# linux-H-zero.net
KiCad netlist of a schematic drawn in Altium Designer
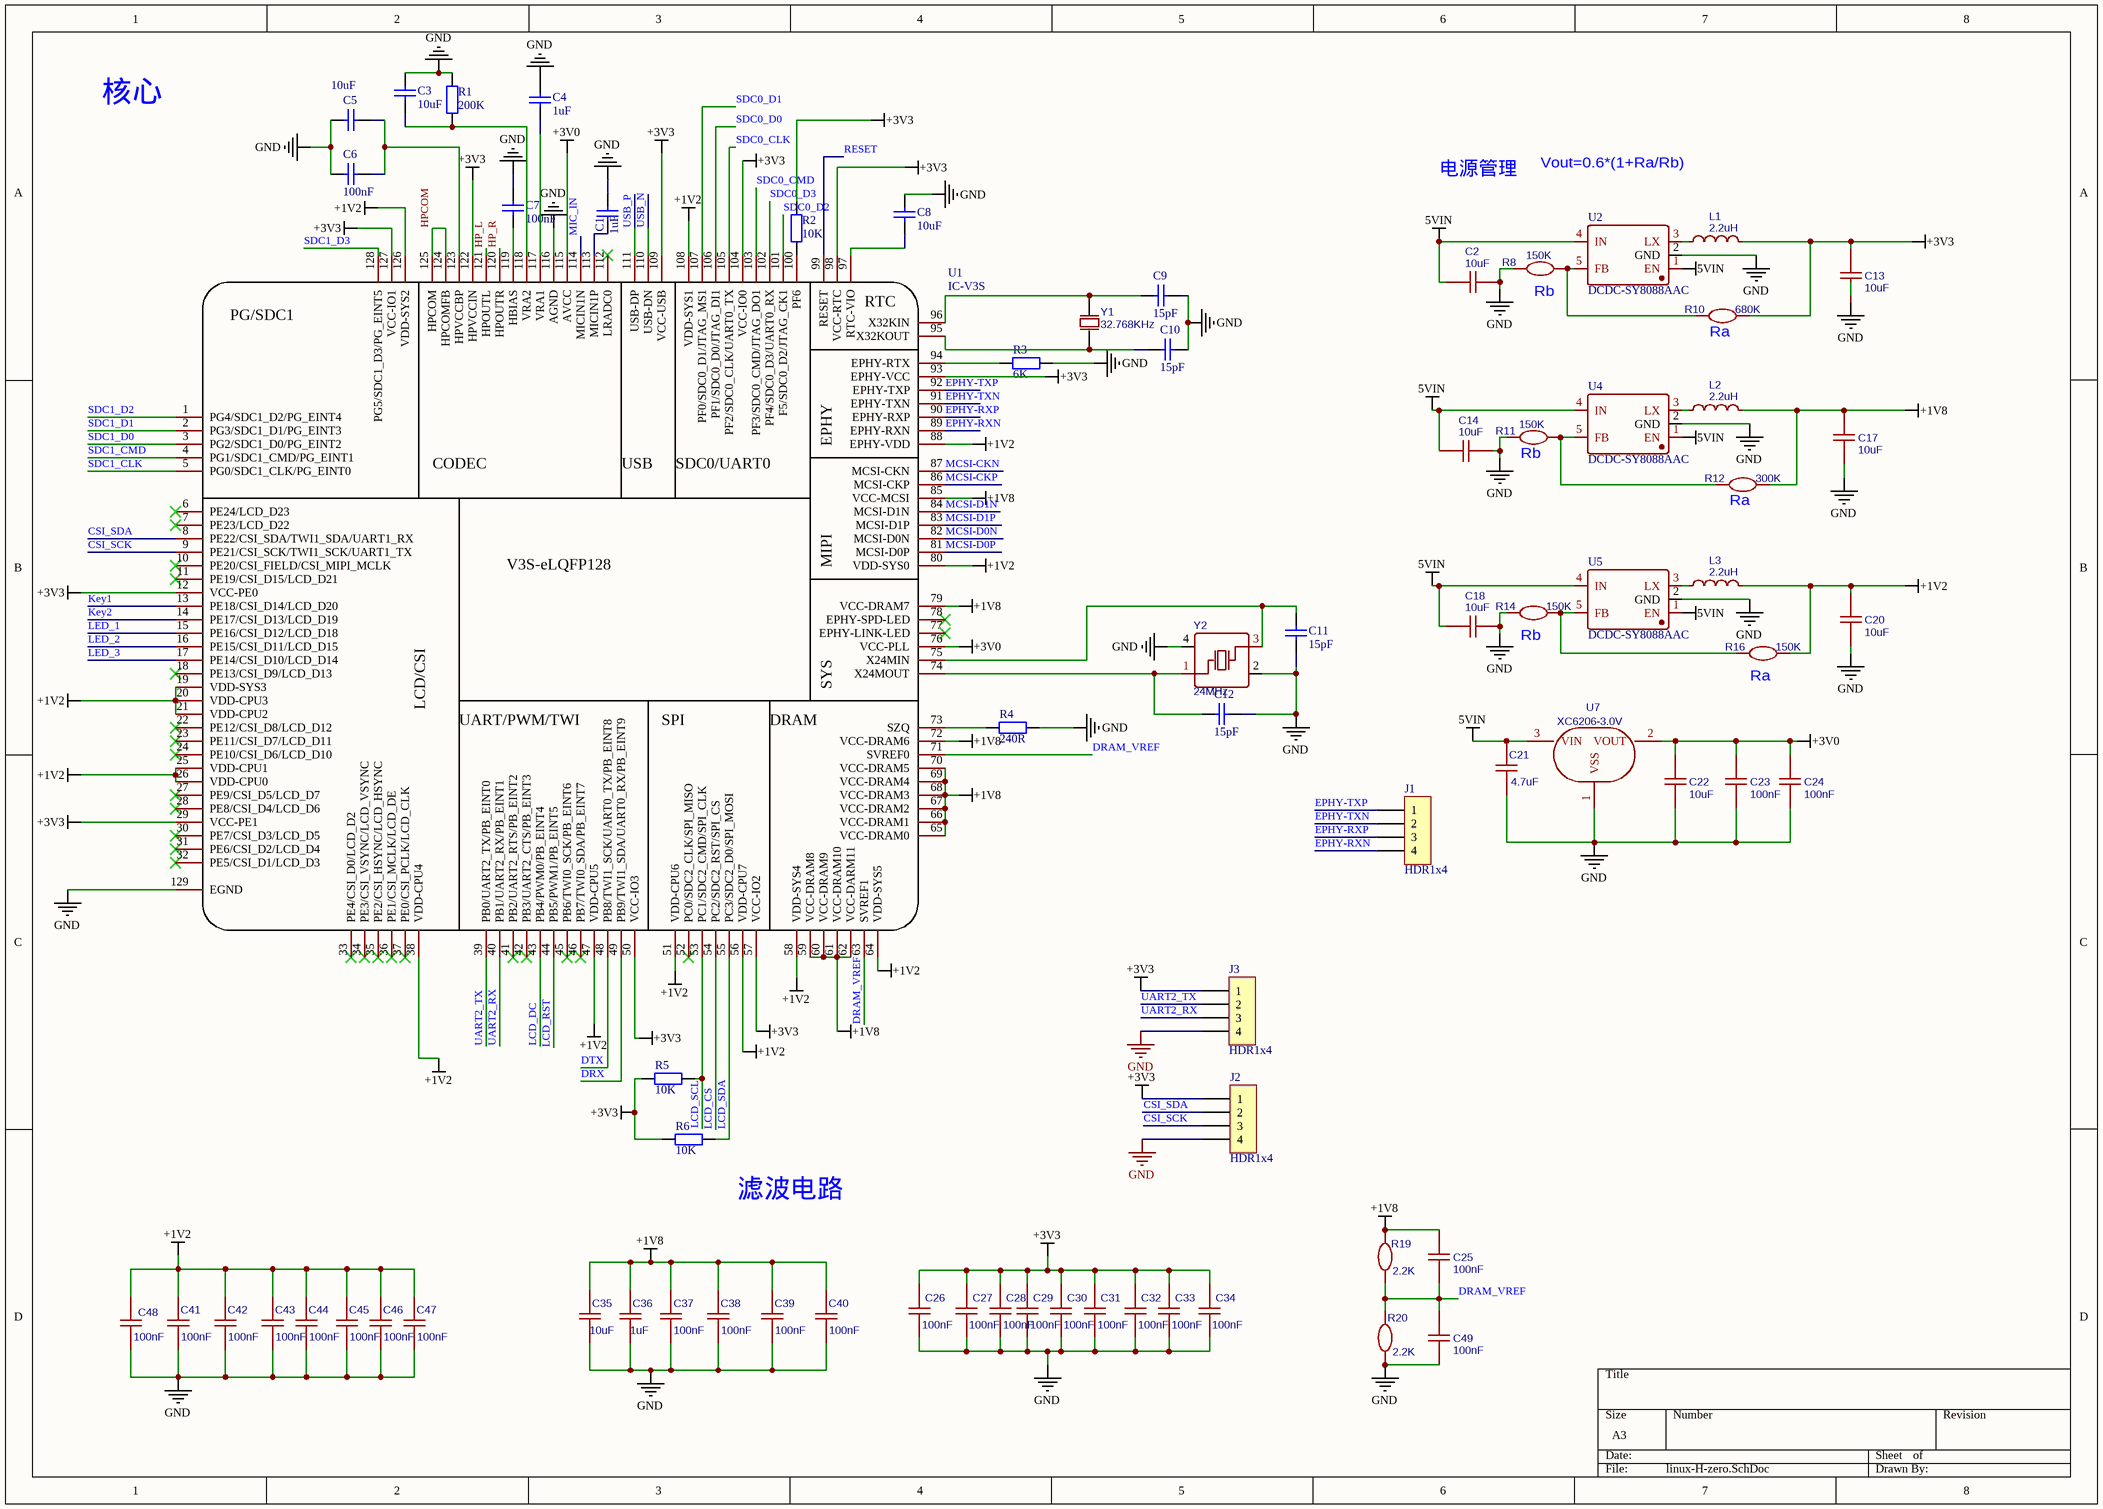
[diagram p0: linux-H-zero.SchDoc]

(export (version "E")
  (design (tool "Eeschema 10.0.6"))
  (components
    (comp (ref "C1") (value "1uF") (footprint "C0603-S") (libsource (lib "贴片") (part "C0603")))
    (comp (ref "C2")
      (value "10uF")
      (footprint "C0603-S")
      (fields
        (field (name "BOM_SUPPLIER PART") "C524952")
        (field (name "BOM_MANUFACTURER PART") "AMK107BJ106MA-T")
        (field (name "CONTRIBUTOR") "LCSC")
      )
      (libsource (lib "altium-import") (part "root_0_10uF_"))
    )
    (comp (ref "C3") (value "10uF") (footprint "C0603-S") (libsource (lib "贴片") (part "C0603")))
    (comp (ref "C4") (value "1uF") (footprint "C0603-S") (libsource (lib "贴片") (part "C0603")))
    (comp (ref "C5") (value "10uF") (footprint "C0603-S") (libsource (lib "贴片") (part "C0603")))
    (comp (ref "C6") (value "100nF") (footprint "C0603-S") (libsource (lib "贴片") (part "C0603")))
    (comp (ref "C7") (value "100nF") (footprint "C0603-S") (libsource (lib "贴片") (part "C0603")))
    (comp (ref "C8") (value "10uF") (footprint "C0603-S") (libsource (lib "贴片") (part "C0603")))
    (comp (ref "C9") (value "15pF") (footprint "C0603-S") (libsource (lib "贴片") (part "C0603")))
    (comp (ref "C10") (value "15pF") (footprint "C0603-S") (libsource (lib "贴片") (part "C0603")))
    (comp (ref "C11") (value "15pF") (footprint "C0603-S") (libsource (lib "贴片") (part "C0603")))
    (comp (ref "C12") (value "15pF") (footprint "C0603-S") (libsource (lib "贴片") (part "C0603")))
    (comp (ref "C13")
      (value "10uF")
      (footprint "C0603-S")
      (fields
        (field (name "BOM_SUPPLIER PART") "C524952")
        (field (name "BOM_MANUFACTURER PART") "AMK107BJ106MA-T")
        (field (name "CONTRIBUTOR") "LCSC")
      )
      (libsource (lib "altium-import") (part "root_1_10uF_"))
    )
    (comp (ref "C14")
      (value "10uF")
      (footprint "C0603-S")
      (fields
        (field (name "BOM_SUPPLIER PART") "C524952")
        (field (name "BOM_MANUFACTURER PART") "AMK107BJ106MA-T")
        (field (name "CONTRIBUTOR") "LCSC")
      )
      (libsource (lib "altium-import") (part "root_0_10uF_"))
    )
    (comp (ref "C17")
      (value "10uF")
      (footprint "C0603-S")
      (fields
        (field (name "BOM_SUPPLIER PART") "C524952")
        (field (name "BOM_MANUFACTURER PART") "AMK107BJ106MA-T")
        (field (name "CONTRIBUTOR") "LCSC")
      )
      (libsource (lib "altium-import") (part "root_1_10uF_"))
    )
    (comp (ref "C18")
      (value "10uF")
      (footprint "C0603-S")
      (fields
        (field (name "BOM_SUPPLIER PART") "C524952")
        (field (name "BOM_MANUFACTURER PART") "AMK107BJ106MA-T")
        (field (name "CONTRIBUTOR") "LCSC")
      )
      (libsource (lib "altium-import") (part "root_0_10uF_"))
    )
    (comp (ref "C20")
      (value "10uF")
      (footprint "C0603-S")
      (fields
        (field (name "BOM_SUPPLIER PART") "C524952")
        (field (name "BOM_MANUFACTURER PART") "AMK107BJ106MA-T")
        (field (name "CONTRIBUTOR") "LCSC")
      )
      (libsource (lib "altium-import") (part "root_1_10uF_"))
    )
    (comp (ref "C21")
      (value "4.7uF")
      (footprint "C0603-S")
      (fields
        (field (name "BOM_SUPPLIER PART") "C524952")
        (field (name "BOM_MANUFACTURER PART") "AMK107BJ106MA-T")
        (field (name "CONTRIBUTOR") "LCSC")
      )
      (libsource (lib "altium-import") (part "root_1_4.7uF_"))
    )
    (comp (ref "C22")
      (value "10uF")
      (footprint "C0603-S")
      (fields
        (field (name "BOM_SUPPLIER PART") "C524952")
        (field (name "BOM_MANUFACTURER PART") "AMK107BJ106MA-T")
        (field (name "CONTRIBUTOR") "LCSC")
      )
      (libsource (lib "altium-import") (part "root_1_10uF_"))
    )
    (comp (ref "C23")
      (value "100nF")
      (footprint "C0603-S")
      (fields
        (field (name "BOM_SUPPLIER PART") "C524952")
        (field (name "BOM_MANUFACTURER PART") "AMK107BJ106MA-T")
        (field (name "CONTRIBUTOR") "LCSC")
      )
      (libsource (lib "altium-import") (part "root_1_100nF_"))
    )
    (comp (ref "C24")
      (value "100nF")
      (footprint "C0603-S")
      (fields
        (field (name "BOM_SUPPLIER PART") "C524952")
        (field (name "BOM_MANUFACTURER PART") "AMK107BJ106MA-T")
        (field (name "CONTRIBUTOR") "LCSC")
      )
      (libsource (lib "altium-import") (part "root_1_100nF_"))
    )
    (comp (ref "C25")
      (value "100nF")
      (footprint "C0603-S")
      (fields
        (field (name "BOM_SUPPLIER PART") "C524952")
        (field (name "BOM_MANUFACTURER PART") "AMK107BJ106MA-T")
        (field (name "CONTRIBUTOR") "LCSC")
      )
      (libsource (lib "altium-import") (part "root_1_100nF_"))
    )
    (comp (ref "C26")
      (value "100nF")
      (footprint "C0603-S")
      (fields
        (field (name "BOM_SUPPLIER PART") "C524952")
        (field (name "BOM_MANUFACTURER PART") "AMK107BJ106MA-T")
        (field (name "CONTRIBUTOR") "LCSC")
      )
      (libsource (lib "altium-import") (part "root_3_100nF_"))
    )
    (comp (ref "C27")
      (value "100nF")
      (footprint "C0603-S")
      (fields
        (field (name "BOM_SUPPLIER PART") "C524952")
        (field (name "BOM_MANUFACTURER PART") "AMK107BJ106MA-T")
        (field (name "CONTRIBUTOR") "LCSC")
      )
      (libsource (lib "altium-import") (part "root_3_100nF_"))
    )
    (comp (ref "C28")
      (value "100nF")
      (footprint "C0603-S")
      (fields
        (field (name "BOM_SUPPLIER PART") "C524952")
        (field (name "BOM_MANUFACTURER PART") "AMK107BJ106MA-T")
        (field (name "CONTRIBUTOR") "LCSC")
      )
      (libsource (lib "altium-import") (part "root_3_100nF_"))
    )
    (comp (ref "C29")
      (value "100nF")
      (footprint "C0603-S")
      (fields
        (field (name "BOM_SUPPLIER PART") "C524952")
        (field (name "BOM_MANUFACTURER PART") "AMK107BJ106MA-T")
        (field (name "CONTRIBUTOR") "LCSC")
      )
      (libsource (lib "altium-import") (part "root_3_100nF_"))
    )
    (comp (ref "C30")
      (value "100nF")
      (footprint "C0603-S")
      (fields
        (field (name "BOM_SUPPLIER PART") "C524952")
        (field (name "BOM_MANUFACTURER PART") "AMK107BJ106MA-T")
        (field (name "CONTRIBUTOR") "LCSC")
      )
      (libsource (lib "altium-import") (part "root_3_100nF_"))
    )
    (comp (ref "C31")
      (value "100nF")
      (footprint "C0603-S")
      (fields
        (field (name "BOM_SUPPLIER PART") "C524952")
        (field (name "BOM_MANUFACTURER PART") "AMK107BJ106MA-T")
        (field (name "CONTRIBUTOR") "LCSC")
      )
      (libsource (lib "altium-import") (part "root_3_100nF_"))
    )
    (comp (ref "C32")
      (value "100nF")
      (footprint "C0603-S")
      (fields
        (field (name "BOM_SUPPLIER PART") "C524952")
        (field (name "BOM_MANUFACTURER PART") "AMK107BJ106MA-T")
        (field (name "CONTRIBUTOR") "LCSC")
      )
      (libsource (lib "altium-import") (part "root_3_100nF_"))
    )
    (comp (ref "C33")
      (value "100nF")
      (footprint "C0603-S")
      (fields
        (field (name "BOM_SUPPLIER PART") "C524952")
        (field (name "BOM_MANUFACTURER PART") "AMK107BJ106MA-T")
        (field (name "CONTRIBUTOR") "LCSC")
      )
      (libsource (lib "altium-import") (part "root_3_100nF_"))
    )
    (comp (ref "C34")
      (value "100nF")
      (footprint "C0603-S")
      (fields
        (field (name "BOM_SUPPLIER PART") "C524952")
        (field (name "BOM_MANUFACTURER PART") "AMK107BJ106MA-T")
        (field (name "CONTRIBUTOR") "LCSC")
      )
      (libsource (lib "altium-import") (part "root_3_100nF_"))
    )
    (comp (ref "C35")
      (value "10uF")
      (footprint "C0603-S")
      (fields
        (field (name "BOM_SUPPLIER PART") "C524952")
        (field (name "BOM_MANUFACTURER PART") "AMK107BJ106MA-T")
        (field (name "CONTRIBUTOR") "LCSC")
      )
      (libsource (lib "altium-import") (part "root_1_10uF_"))
    )
    (comp (ref "C36")
      (value "1uF")
      (footprint "C0603-S")
      (fields
        (field (name "BOM_SUPPLIER PART") "C524952")
        (field (name "BOM_MANUFACTURER PART") "AMK107BJ106MA-T")
        (field (name "CONTRIBUTOR") "LCSC")
      )
      (libsource (lib "altium-import") (part "root_1_1uF_"))
    )
    (comp (ref "C37")
      (value "100nF")
      (footprint "C0603-S")
      (fields
        (field (name "BOM_SUPPLIER PART") "C524952")
        (field (name "BOM_MANUFACTURER PART") "AMK107BJ106MA-T")
        (field (name "CONTRIBUTOR") "LCSC")
      )
      (libsource (lib "altium-import") (part "root_1_100nF_"))
    )
    (comp (ref "C38")
      (value "100nF")
      (footprint "C0603-S")
      (fields
        (field (name "BOM_SUPPLIER PART") "C524952")
        (field (name "BOM_MANUFACTURER PART") "AMK107BJ106MA-T")
        (field (name "CONTRIBUTOR") "LCSC")
      )
      (libsource (lib "altium-import") (part "root_1_100nF_"))
    )
    (comp (ref "C39")
      (value "100nF")
      (footprint "C0603-S")
      (fields
        (field (name "BOM_SUPPLIER PART") "C524952")
        (field (name "BOM_MANUFACTURER PART") "AMK107BJ106MA-T")
        (field (name "CONTRIBUTOR") "LCSC")
      )
      (libsource (lib "altium-import") (part "root_1_100nF_"))
    )
    (comp (ref "C40")
      (value "100nF")
      (footprint "C0603-S")
      (fields
        (field (name "BOM_SUPPLIER PART") "C524952")
        (field (name "BOM_MANUFACTURER PART") "AMK107BJ106MA-T")
        (field (name "CONTRIBUTOR") "LCSC")
      )
      (libsource (lib "altium-import") (part "root_1_100nF_"))
    )
    (comp (ref "C41")
      (value "100nF")
      (footprint "C0603-S")
      (fields
        (field (name "BOM_SUPPLIER PART") "C524952")
        (field (name "BOM_MANUFACTURER PART") "AMK107BJ106MA-T")
        (field (name "CONTRIBUTOR") "LCSC")
      )
      (libsource (lib "altium-import") (part "root_1_100nF_"))
    )
    (comp (ref "C42")
      (value "100nF")
      (footprint "C0603-S")
      (fields
        (field (name "BOM_SUPPLIER PART") "C524952")
        (field (name "BOM_MANUFACTURER PART") "AMK107BJ106MA-T")
        (field (name "CONTRIBUTOR") "LCSC")
      )
      (libsource (lib "altium-import") (part "root_1_100nF_"))
    )
    (comp (ref "C43")
      (value "100nF")
      (footprint "C0603-S")
      (fields
        (field (name "BOM_SUPPLIER PART") "C524952")
        (field (name "BOM_MANUFACTURER PART") "AMK107BJ106MA-T")
        (field (name "CONTRIBUTOR") "LCSC")
      )
      (libsource (lib "altium-import") (part "root_1_100nF_"))
    )
    (comp (ref "C44")
      (value "100nF")
      (footprint "C0603-S")
      (fields
        (field (name "BOM_SUPPLIER PART") "C524952")
        (field (name "BOM_MANUFACTURER PART") "AMK107BJ106MA-T")
        (field (name "CONTRIBUTOR") "LCSC")
      )
      (libsource (lib "altium-import") (part "root_1_100nF_"))
    )
    (comp (ref "C45")
      (value "100nF")
      (footprint "C0603-S")
      (fields
        (field (name "BOM_SUPPLIER PART") "C524952")
        (field (name "BOM_MANUFACTURER PART") "AMK107BJ106MA-T")
        (field (name "CONTRIBUTOR") "LCSC")
      )
      (libsource (lib "altium-import") (part "root_1_100nF_"))
    )
    (comp (ref "C46")
      (value "100nF")
      (footprint "C0603-S")
      (fields
        (field (name "BOM_SUPPLIER PART") "C524952")
        (field (name "BOM_MANUFACTURER PART") "AMK107BJ106MA-T")
        (field (name "CONTRIBUTOR") "LCSC")
      )
      (libsource (lib "altium-import") (part "root_1_100nF_"))
    )
    (comp (ref "C47")
      (value "100nF")
      (footprint "C0603-S")
      (fields
        (field (name "BOM_SUPPLIER PART") "C524952")
        (field (name "BOM_MANUFACTURER PART") "AMK107BJ106MA-T")
        (field (name "CONTRIBUTOR") "LCSC")
      )
      (libsource (lib "altium-import") (part "root_1_100nF_"))
    )
    (comp (ref "C48")
      (value "100nF")
      (footprint "C0603-S")
      (fields
        (field (name "BOM_SUPPLIER PART") "C524952")
        (field (name "BOM_MANUFACTURER PART") "AMK107BJ106MA-T")
        (field (name "CONTRIBUTOR") "LCSC")
      )
      (libsource (lib "altium-import") (part "root_1_100nF_"))
    )
    (comp (ref "C49")
      (value "100nF")
      (footprint "C0603-S")
      (fields
        (field (name "BOM_SUPPLIER PART") "C524952")
        (field (name "BOM_MANUFACTURER PART") "AMK107BJ106MA-T")
        (field (name "CONTRIBUTOR") "LCSC")
      )
      (libsource (lib "altium-import") (part "root_1_100nF_"))
    )
    (comp (ref "J1")
      (value "HDR1x4")
      (footprint "T-4PIN")
      (description "Connector")
      (libsource (lib "插件") (part "HDR1x4"))
    )
    (comp (ref "J2")
      (value "HDR1x4")
      (footprint "T-4PIN")
      (description "Connector")
      (libsource (lib "插件") (part "HDR1x4"))
    )
    (comp (ref "J3")
      (value "HDR1x4")
      (footprint "T-4PIN")
      (description "Connector")
      (libsource (lib "插件") (part "HDR1x4"))
    )
    (comp (ref "L1")
      (value "2.2uH")
      (footprint "L0805")
      (fields
        (field (name "BOM_MANUFACTURER PART") "CMI201209U2R2KT")
        (field (name "BOM_SUPPLIER PART") "C1043")
      )
      (libsource (lib "altium-import") (part "root_0_2.2uH_"))
    )
    (comp (ref "L2")
      (value "2.2uH")
      (footprint "L0805")
      (fields
        (field (name "BOM_MANUFACTURER PART") "CMI201209U2R2KT")
        (field (name "BOM_SUPPLIER PART") "C1043")
      )
      (libsource (lib "altium-import") (part "root_0_2.2uH_"))
    )
    (comp (ref "L3")
      (value "2.2uH")
      (footprint "L0805")
      (fields
        (field (name "BOM_MANUFACTURER PART") "CMI201209U2R2KT")
        (field (name "BOM_SUPPLIER PART") "C1043")
      )
      (libsource (lib "altium-import") (part "root_0_2.2uH_"))
    )
    (comp (ref "R1") (value "200K") (footprint "R0603-S") (libsource (lib "") (part "R0603_1")))
    (comp (ref "R2") (value "10K") (footprint "R0603-S") (libsource (lib "") (part "R0603_1")))
    (comp (ref "R3") (value "6K") (footprint "R0603-S") (libsource (lib "贴片") (part "R0603")))
    (comp (ref "R4") (value "240R") (footprint "R0603-S") (libsource (lib "贴片") (part "R0603")))
    (comp (ref "R5") (value "10K") (footprint "R0603-S") (libsource (lib "贴片") (part "R0603")))
    (comp (ref "R6") (value "10K") (footprint "R0603-S") (libsource (lib "贴片") (part "R0603")))
    (comp (ref "R8")
      (value "150K")
      (footprint "R0603-S")
      (fields
        (field (name "BOM_SUPPLIER PART") "C465746")
        (field (name "BOM_MANUFACTURER PART") "ERA3ARB103V")
        (field (name "CONTRIBUTOR") "LCSC")
      )
      (libsource (lib "altium-import") (part "root_0_150K_"))
    )
    (comp (ref "R10")
      (value "680K")
      (footprint "R0603-S")
      (fields
        (field (name "BOM_SUPPLIER PART") "C465746")
        (field (name "BOM_MANUFACTURER PART") "ERA3ARB103V")
        (field (name "CONTRIBUTOR") "LCSC")
      )
      (libsource (lib "altium-import") (part "root_0_680K_"))
    )
    (comp (ref "R11")
      (value "150K")
      (footprint "R0603-S")
      (fields
        (field (name "BOM_SUPPLIER PART") "C465746")
        (field (name "BOM_MANUFACTURER PART") "ERA3ARB103V")
        (field (name "CONTRIBUTOR") "LCSC")
      )
      (libsource (lib "altium-import") (part "root_0_150K_"))
    )
    (comp (ref "R12")
      (value "300K")
      (footprint "R0603-S")
      (fields
        (field (name "BOM_SUPPLIER PART") "C465746")
        (field (name "BOM_MANUFACTURER PART") "ERA3ARB103V")
        (field (name "CONTRIBUTOR") "LCSC")
      )
      (libsource (lib "altium-import") (part "root_0_300K_"))
    )
    (comp (ref "R14")
      (value "150K")
      (footprint "R0603-S")
      (fields
        (field (name "BOM_SUPPLIER PART") "C465746")
        (field (name "BOM_MANUFACTURER PART") "ERA3ARB103V")
        (field (name "CONTRIBUTOR") "LCSC")
      )
      (libsource (lib "altium-import") (part "root_0_150K_"))
    )
    (comp (ref "R16")
      (value "150K")
      (footprint "R0603-S")
      (fields
        (field (name "BOM_SUPPLIER PART") "C465746")
        (field (name "BOM_MANUFACTURER PART") "ERA3ARB103V")
        (field (name "CONTRIBUTOR") "LCSC")
      )
      (libsource (lib "altium-import") (part "root_0_150K_"))
    )
    (comp (ref "R19")
      (value "2.2K")
      (footprint "R0603-S")
      (fields
        (field (name "BOM_SUPPLIER PART") "C465746")
        (field (name "BOM_MANUFACTURER PART") "ERA3ARB103V")
        (field (name "CONTRIBUTOR") "LCSC")
      )
      (libsource (lib "altium-import") (part "root_1_2.2K_"))
    )
    (comp (ref "R20")
      (value "2.2K")
      (footprint "R0603-S")
      (fields
        (field (name "BOM_SUPPLIER PART") "C465746")
        (field (name "BOM_MANUFACTURER PART") "ERA3ARB103V")
        (field (name "CONTRIBUTOR") "LCSC")
      )
      (libsource (lib "altium-import") (part "root_1_2.2K_"))
    )
    (comp (ref "U1") (value "IC-V3S") (footprint "IC-V3S") (libsource (lib "贴片") (part "IC-V3S")))
    (comp (ref "U2")
      (value "DCDC-SY8088AAC")
      (footprint "SOT-23-5_L3.0-W1.7-P0.95-LS2.8-BR")
      (libsource (lib "贴片") (part "DCDC-SY8088AAC"))
    )
    (comp (ref "U4")
      (value "DCDC-SY8088AAC")
      (footprint "SOT-23-5_L3.0-W1.7-P0.95-LS2.8-BR")
      (libsource (lib "贴片") (part "DCDC-SY8088AAC"))
    )
    (comp (ref "U5")
      (value "DCDC-SY8088AAC")
      (footprint "SOT-23-5_L3.0-W1.7-P0.95-LS2.8-BR")
      (libsource (lib "贴片") (part "DCDC-SY8088AAC"))
    )
    (comp (ref "U7")
      (value "XC6206-3.0V")
      (footprint "SOT-23")
      (fields
        (field (name "BOM_SUPPLIER PART") "C17167")
        (field (name "BOM_MANUFACTURER PART") "XC6206P232MR")
        (field (name "CONTRIBUTOR") "LCSC")
      )
      (libsource (lib "altium-import") (part "root_0_XC6206-3.0V_"))
    )
    (comp (ref "Y1")
      (value "32.768KHz")
      (footprint "OSC-SMD_L3.2-W1.5")
      (fields
        (field (name "BOM_SUPPLIER PART") "C271654")
        (field (name "BOM_MANUFACTURER PART") "SF32K32768D31T-12.5")
        (field (name "CONTRIBUTOR") "LCSC")
      )
      (libsource (lib "贴片") (part "Y-32.768KHz"))
    )
    (comp (ref "Y2")
      (value "24MHz")
      (footprint "OSC-SMD_4P-L3.2-W2.5-BL")
      (fields
        (field (name "BOM_MANUFACTURER PART") "X322524MSB4SI")
        (field (name "BOM_SUPPLIER PART") "C15643")
      )
      (libsource (lib "贴片") (part "Y-24MHz"))
    )
  )
  (nets
    (net (code "1") (name "+1V2") (class "Default")
      (node (ref "C20") (pin "2") (pinfunction "2_2") (pintype "passive"))
      (node (ref "C41") (pin "2") (pinfunction "2_2") (pintype "passive"))
      (node (ref "C42") (pin "2") (pinfunction "2_2") (pintype "passive"))
      (node (ref "C43") (pin "2") (pinfunction "2_2") (pintype "passive"))
      (node (ref "C44") (pin "2") (pinfunction "2_2") (pintype "passive"))
      (node (ref "C45") (pin "2") (pinfunction "2_2") (pintype "passive"))
      (node (ref "C46") (pin "2") (pinfunction "2_2") (pintype "passive"))
      (node (ref "C47") (pin "2") (pinfunction "2_2") (pintype "passive"))
      (node (ref "C48") (pin "2") (pinfunction "2_2") (pintype "passive"))
      (node (ref "L3") (pin "2") (pinfunction "2_2") (pintype "passive"))
      (node (ref "R16") (pin "2") (pinfunction "2_2") (pintype "passive"))
      (node (ref "U1") (pin "108") (pinfunction "VDD-SYS1_108") (pintype "passive"))
      (node (ref "U1") (pin "126") (pinfunction "VDD-SYS2_126") (pintype "passive"))
      (node (ref "U1") (pin "19") (pinfunction "VDD-SYS3_19") (pintype "passive"))
      (node (ref "U1") (pin "20") (pinfunction "VDD-CPU3_20") (pintype "passive"))
      (node (ref "U1") (pin "21") (pinfunction "VDD-CPU2_21") (pintype "passive"))
      (node (ref "U1") (pin "25") (pinfunction "VDD-CPU1_25") (pintype "passive"))
      (node (ref "U1") (pin "26") (pinfunction "VDD-CPU0_26") (pintype "passive"))
      (node (ref "U1") (pin "38") (pinfunction "VDD-CPU4_38") (pintype "passive"))
      (node (ref "U1") (pin "47") (pinfunction "VDD-CPU5_47") (pintype "passive"))
      (node (ref "U1") (pin "51") (pinfunction "VDD-CPU6_51") (pintype "passive"))
      (node (ref "U1") (pin "56") (pinfunction "VDD-CPU7_56") (pintype "passive"))
      (node (ref "U1") (pin "58") (pinfunction "VDD-SYS4_58") (pintype "passive"))
      (node (ref "U1") (pin "64") (pinfunction "VDD-SYS5_64") (pintype "passive"))
      (node (ref "U1") (pin "80") (pinfunction "VDD-SYS0_80") (pintype "passive"))
      (node (ref "U1") (pin "88") (pinfunction "EPHY-VDD_88") (pintype "passive"))
    )
    (net (code "2") (name "+1V8") (class "Default")
      (node (ref "C17") (pin "2") (pinfunction "2_2") (pintype "passive"))
      (node (ref "C25") (pin "2") (pinfunction "2_2") (pintype "passive"))
      (node (ref "C35") (pin "2") (pinfunction "2_2") (pintype "passive"))
      (node (ref "C36") (pin "2") (pinfunction "2_2") (pintype "passive"))
      (node (ref "C37") (pin "2") (pinfunction "2_2") (pintype "passive"))
      (node (ref "C38") (pin "2") (pinfunction "2_2") (pintype "passive"))
      (node (ref "C39") (pin "2") (pinfunction "2_2") (pintype "passive"))
      (node (ref "C40") (pin "2") (pinfunction "2_2") (pintype "passive"))
      (node (ref "L2") (pin "2") (pinfunction "2_2") (pintype "passive"))
      (node (ref "R12") (pin "2") (pinfunction "2_2") (pintype "passive"))
      (node (ref "R19") (pin "2") (pinfunction "2_2") (pintype "passive"))
      (node (ref "U1") (pin "59") (pinfunction "VCC-DRAM8_59") (pintype "passive"))
      (node (ref "U1") (pin "60") (pinfunction "VCC-DRAM9_60") (pintype "passive"))
      (node (ref "U1") (pin "61") (pinfunction "VCC-DRAM10_61") (pintype "passive"))
      (node (ref "U1") (pin "62") (pinfunction "VCC-DARM11_62") (pintype "passive"))
      (node (ref "U1") (pin "65") (pinfunction "VCC-DRAM0_65") (pintype "passive"))
      (node (ref "U1") (pin "66") (pinfunction "VCC-DRAM1_66") (pintype "passive"))
      (node (ref "U1") (pin "67") (pinfunction "VCC-DRAM2_67") (pintype "passive"))
      (node (ref "U1") (pin "68") (pinfunction "VCC-DRAM3_68") (pintype "passive"))
      (node (ref "U1") (pin "69") (pinfunction "VCC-DRAM4_69") (pintype "passive"))
      (node (ref "U1") (pin "70") (pinfunction "VCC-DRAM5_70") (pintype "passive"))
      (node (ref "U1") (pin "72") (pinfunction "VCC-DRAM6_72") (pintype "passive"))
      (node (ref "U1") (pin "79") (pinfunction "VCC-DRAM7_79") (pintype "passive"))
      (node (ref "U1") (pin "85") (pinfunction "VCC-MCSI_85") (pintype "passive"))
    )
    (net (code "3") (name "+3V0") (class "Default")
      (node (ref "C22") (pin "2") (pinfunction "2_2") (pintype "passive"))
      (node (ref "C23") (pin "2") (pinfunction "2_2") (pintype "passive"))
      (node (ref "C24") (pin "2") (pinfunction "2_2") (pintype "passive"))
      (node (ref "U1") (pin "115") (pinfunction "AVCC_115") (pintype "passive"))
      (node (ref "U1") (pin "76") (pinfunction "VCC-PLL_76") (pintype "passive"))
      (node (ref "U7") (pin "2") (pinfunction "VOUT_2") (pintype "passive"))
    )
    (net (code "4") (name "+3V3") (class "Default")
      (node (ref "C13") (pin "2") (pinfunction "2_2") (pintype "passive"))
      (node (ref "C26") (pin "1") (pinfunction "1_1") (pintype "passive"))
      (node (ref "C27") (pin "1") (pinfunction "1_1") (pintype "passive"))
      (node (ref "C28") (pin "1") (pinfunction "1_1") (pintype "passive"))
      (node (ref "C29") (pin "1") (pinfunction "1_1") (pintype "passive"))
      (node (ref "C30") (pin "1") (pinfunction "1_1") (pintype "passive"))
      (node (ref "C31") (pin "1") (pinfunction "1_1") (pintype "passive"))
      (node (ref "C32") (pin "1") (pinfunction "1_1") (pintype "passive"))
      (node (ref "C33") (pin "1") (pinfunction "1_1") (pintype "passive"))
      (node (ref "C34") (pin "1") (pinfunction "1_1") (pintype "passive"))
      (node (ref "J2") (pin "1") (pinfunction "1_1") (pintype "passive"))
      (node (ref "J3") (pin "1") (pinfunction "1_1") (pintype "passive"))
      (node (ref "L1") (pin "2") (pinfunction "2_2") (pintype "passive"))
      (node (ref "R10") (pin "2") (pinfunction "2_2") (pintype "passive"))
      (node (ref "R2") (pin "2") (pinfunction "2_2") (pintype "passive"))
      (node (ref "R5") (pin "2") (pinfunction "2_2") (pintype "passive"))
      (node (ref "R6") (pin "2") (pinfunction "2_2") (pintype "passive"))
      (node (ref "U1") (pin "104") (pinfunction "VCC-IO0_104") (pintype "passive"))
      (node (ref "U1") (pin "109") (pinfunction "VCC-USB_109") (pintype "passive"))
      (node (ref "U1") (pin "12") (pinfunction "VCC-PE0_12") (pintype "passive"))
      (node (ref "U1") (pin "122") (pinfunction "HPVCCIN_122") (pintype "passive"))
      (node (ref "U1") (pin "127") (pinfunction "VCC-IO1_127") (pintype "passive"))
      (node (ref "U1") (pin "29") (pinfunction "VCC-PE1_29") (pintype "passive"))
      (node (ref "U1") (pin "50") (pinfunction "VCC-IO3_50") (pintype "passive"))
      (node (ref "U1") (pin "57") (pinfunction "VCC-IO2_57") (pintype "passive"))
      (node (ref "U1") (pin "93") (pinfunction "EPHY-VCC_93") (pintype "passive"))
      (node (ref "U1") (pin "98") (pinfunction "VCC-RTC_98") (pintype "passive"))
    )
    (net (code "5") (name "/CSI_SCK") (class "Default")
      (node (ref "J2") (pin "3") (pinfunction "3_3") (pintype "passive"))
      (node (ref "U1") (pin "9") (pinfunction "PE21/CSI_SCK/TWI1_SCK/UART1_TX_9") (pintype "passive"))
    )
    (net (code "6") (name "/CSI_SDA") (class "Default")
      (node (ref "J2") (pin "2") (pinfunction "2_2") (pintype "passive"))
      (node (ref "U1") (pin "8") (pinfunction "PE22/CSI_SDA/TWI1_SDA/UART1_RX_8") (pintype "passive"))
    )
    (net (code "7") (name "/DRAM_VREF") (class "Default")
      (node (ref "C25") (pin "1") (pinfunction "1_1") (pintype "passive"))
      (node (ref "C49") (pin "2") (pinfunction "2_2") (pintype "passive"))
      (node (ref "R19") (pin "1") (pinfunction "1_1") (pintype "passive"))
      (node (ref "R20") (pin "2") (pinfunction "2_2") (pintype "passive"))
      (node (ref "U1") (pin "63") (pinfunction "SVREF1_63") (pintype "passive"))
      (node (ref "U1") (pin "71") (pinfunction "SVREF0_71") (pintype "passive"))
    )
    (net (code "8") (name "/DRX") (class "Default")
      (node (ref "U1") (pin "49") (pinfunction "PB9/TWI1_SDA/UART0_RX/PB_EINT9_49") (pintype "passive"))
    )
    (net (code "9") (name "/DTX") (class "Default")
      (node (ref "U1") (pin "48") (pinfunction "PB8/TWI1_SCK/UART0_TX/PB_EINT8_48") (pintype "passive"))
    )
    (net (code "10") (name "/EPHY-RXN") (class "Default")
      (node (ref "J1") (pin "4") (pinfunction "4_4") (pintype "passive"))
      (node (ref "U1") (pin "89") (pinfunction "EPHY-RXN_89") (pintype "passive"))
    )
    (net (code "11") (name "/EPHY-RXP") (class "Default")
      (node (ref "J1") (pin "3") (pinfunction "3_3") (pintype "passive"))
      (node (ref "U1") (pin "90") (pinfunction "EPHY-RXP_90") (pintype "passive"))
    )
    (net (code "12") (name "/EPHY-TXN") (class "Default")
      (node (ref "J1") (pin "2") (pinfunction "2_2") (pintype "passive"))
      (node (ref "U1") (pin "91") (pinfunction "EPHY-TXN_91") (pintype "passive"))
    )
    (net (code "13") (name "/EPHY-TXP") (class "Default")
      (node (ref "J1") (pin "1") (pinfunction "1_1") (pintype "passive"))
      (node (ref "U1") (pin "92") (pinfunction "EPHY-TXP_92") (pintype "passive"))
    )
    (net (code "14") (name "/HPCOM") (class "Default")
      (node (ref "U1") (pin "124") (pinfunction "HPCOMFB_124") (pintype "passive"))
      (node (ref "U1") (pin "125") (pinfunction "HPCOM_125") (pintype "passive"))
    )
    (net (code "15") (name "/HP_L") (class "Default")
      (node (ref "U1") (pin "121") (pinfunction "HPOUTL_121") (pintype "passive"))
    )
    (net (code "16") (name "/HP_R") (class "Default")
      (node (ref "U1") (pin "120") (pinfunction "HPOUTR_120") (pintype "passive"))
    )
    (net (code "17") (name "/Key1") (class "Default")
      (node (ref "U1") (pin "13") (pinfunction "PE18/CSI_D14/LCD_D20_13") (pintype "passive"))
    )
    (net (code "18") (name "/Key2") (class "Default")
      (node (ref "U1") (pin "14") (pinfunction "PE17/CSI_D13/LCD_D19_14") (pintype "passive"))
    )
    (net (code "19") (name "/LCD_CS") (class "Default")
      (node (ref "U1") (pin "54") (pinfunction "PC2/SDC2_RST/SPI_CS_54") (pintype "passive"))
    )
    (net (code "20") (name "/LCD_DC") (class "Default")
      (node (ref "U1") (pin "43") (pinfunction "PB4/PWM0/PB_EINT4_43") (pintype "passive"))
    )
    (net (code "21") (name "/LCD_RST") (class "Default")
      (node (ref "U1") (pin "44") (pinfunction "PB5/PWM1/PB_EINT5_44") (pintype "passive"))
    )
    (net (code "22") (name "/LCD_SCL") (class "Default")
      (node (ref "R5") (pin "1") (pinfunction "1_1") (pintype "passive"))
      (node (ref "U1") (pin "53") (pinfunction "PC1/SDC2_CMD/SPI_CLK_53") (pintype "passive"))
    )
    (net (code "23") (name "/LCD_SDA") (class "Default")
      (node (ref "R6") (pin "1") (pinfunction "1_1") (pintype "passive"))
      (node (ref "U1") (pin "55") (pinfunction "PC3/SDC2_D0/SPI_MOSI_55") (pintype "passive"))
    )
    (net (code "24") (name "/LED_1") (class "Default")
      (node (ref "U1") (pin "15") (pinfunction "PE16/CSI_D12/LCD_D18_15") (pintype "passive"))
    )
    (net (code "25") (name "/LED_2") (class "Default")
      (node (ref "U1") (pin "16") (pinfunction "PE15/CSI_D11/LCD_D15_16") (pintype "passive"))
    )
    (net (code "26") (name "/LED_3") (class "Default")
      (node (ref "U1") (pin "17") (pinfunction "PE14/CSI_D10/LCD_D14_17") (pintype "passive"))
    )
    (net (code "27") (name "/MCSI-CKN") (class "Default")
      (node (ref "U1") (pin "87") (pinfunction "MCSI-CKN_87") (pintype "passive"))
    )
    (net (code "28") (name "/MCSI-CKP") (class "Default")
      (node (ref "U1") (pin "86") (pinfunction "MCSI-CKP_86") (pintype "passive"))
    )
    (net (code "29") (name "/MCSI-D0N") (class "Default")
      (node (ref "U1") (pin "82") (pinfunction "MCSI-D0N_82") (pintype "passive"))
    )
    (net (code "30") (name "/MCSI-D0P") (class "Default")
      (node (ref "U1") (pin "81") (pinfunction "MCSI-D0P_81") (pintype "passive"))
    )
    (net (code "31") (name "/MCSI-D1N") (class "Default")
      (node (ref "U1") (pin "84") (pinfunction "MCSI-D1N_84") (pintype "passive"))
    )
    (net (code "32") (name "/MCSI-D1P") (class "Default")
      (node (ref "U1") (pin "83") (pinfunction "MCSI-D1P_83") (pintype "passive"))
    )
    (net (code "33") (name "/MIC_IN") (class "Default")
      (node (ref "U1") (pin "114") (pinfunction "MICIN1N_114") (pintype "passive"))
    )
    (net (code "34") (name "/RESET") (class "Default")
      (node (ref "U1") (pin "99") (pinfunction "RESET_99") (pintype "passive"))
    )
    (net (code "35") (name "/SDC0_CLK") (class "Default")
      (node (ref "U1") (pin "105") (pinfunction "PF2/SDC0_CLK/UART0_TX_105") (pintype "passive"))
    )
    (net (code "36") (name "/SDC0_CMD") (class "Default")
      (node (ref "U1") (pin "103") (pinfunction "PF3/SDC0_CMD/JTAG_DO1_103") (pintype "passive"))
    )
    (net (code "37") (name "/SDC0_D0") (class "Default")
      (node (ref "U1") (pin "106") (pinfunction "PF1/SDC0_D0/JTAG_DI1_106") (pintype "passive"))
    )
    (net (code "38") (name "/SDC0_D1") (class "Default")
      (node (ref "U1") (pin "107") (pinfunction "PF0/SDC0_D1/JTAG_MS1_107") (pintype "passive"))
    )
    (net (code "39") (name "/SDC0_D2") (class "Default")
      (node (ref "U1") (pin "101") (pinfunction "F5/SDC0_D2/JTAG_CK1_101") (pintype "passive"))
    )
    (net (code "40") (name "/SDC0_D3") (class "Default")
      (node (ref "U1") (pin "102") (pinfunction "PF4/SDC0_D3/UART0_RX_102") (pintype "passive"))
    )
    (net (code "41") (name "/SDC1_CLK") (class "Default")
      (node (ref "U1") (pin "5") (pinfunction "PG0/SDC1_CLK/PG_EINT0_5") (pintype "passive"))
    )
    (net (code "42") (name "/SDC1_CMD") (class "Default")
      (node (ref "U1") (pin "4") (pinfunction "PG1/SDC1_CMD/PG_EINT1_4") (pintype "passive"))
    )
    (net (code "43") (name "/SDC1_D0") (class "Default")
      (node (ref "U1") (pin "3") (pinfunction "PG2/SDC1_D0/PG_EINT2_3") (pintype "passive"))
    )
    (net (code "44") (name "/SDC1_D1") (class "Default")
      (node (ref "U1") (pin "2") (pinfunction "PG3/SDC1_D1/PG_EINT3_2") (pintype "passive"))
    )
    (net (code "45") (name "/SDC1_D2") (class "Default")
      (node (ref "U1") (pin "1") (pinfunction "PG4/SDC1_D2/PG_EINT4_1") (pintype "passive"))
    )
    (net (code "46") (name "/SDC1_D3") (class "Default")
      (node (ref "U1") (pin "128") (pinfunction "PG5/SDC1_D3/PG_EINT5_128") (pintype "passive"))
    )
    (net (code "47") (name "/UART2_RX") (class "Default")
      (node (ref "J3") (pin "3") (pinfunction "3_3") (pintype "passive"))
      (node (ref "U1") (pin "40") (pinfunction "PB1/UART2_RX/PB_EINT1_40") (pintype "passive"))
    )
    (net (code "48") (name "/UART2_TX") (class "Default")
      (node (ref "J3") (pin "2") (pinfunction "2_2") (pintype "passive"))
      (node (ref "U1") (pin "39") (pinfunction "PB0/UART2_TX/PB_EINT0_39") (pintype "passive"))
    )
    (net (code "49") (name "/USB_N") (class "Default")
      (node (ref "U1") (pin "110") (pinfunction "USB-DN_110") (pintype "passive"))
    )
    (net (code "50") (name "/USB_P") (class "Default")
      (node (ref "U1") (pin "111") (pinfunction "USB-DP_111") (pintype "passive"))
    )
    (net (code "51") (name "5VIN") (class "Default")
      (node (ref "C14") (pin "1") (pinfunction "1_1") (pintype "passive"))
      (node (ref "C18") (pin "1") (pinfunction "1_1") (pintype "passive"))
      (node (ref "C2") (pin "1") (pinfunction "1_1") (pintype "passive"))
      (node (ref "C21") (pin "2") (pinfunction "2_2") (pintype "passive"))
      (node (ref "U2") (pin "1") (pinfunction "EN_1") (pintype "passive"))
      (node (ref "U2") (pin "4") (pinfunction "IN_4") (pintype "passive"))
      (node (ref "U4") (pin "1") (pinfunction "EN_1") (pintype "passive"))
      (node (ref "U4") (pin "4") (pinfunction "IN_4") (pintype "passive"))
      (node (ref "U5") (pin "1") (pinfunction "EN_1") (pintype "passive"))
      (node (ref "U5") (pin "4") (pinfunction "IN_4") (pintype "passive"))
      (node (ref "U7") (pin "3") (pinfunction "VIN_3") (pintype "passive"))
    )
    (net (code "52") (name "GND") (class "Default")
      (node (ref "C1") (pin "2") (pinfunction "2_2") (pintype "passive"))
      (node (ref "C10") (pin "2") (pinfunction "2_2") (pintype "passive"))
      (node (ref "C11") (pin "1") (pinfunction "1_1") (pintype "passive"))
      (node (ref "C12") (pin "2") (pinfunction "2_2") (pintype "passive"))
      (node (ref "C13") (pin "1") (pinfunction "1_1") (pintype "passive"))
      (node (ref "C14") (pin "2") (pinfunction "2_2") (pintype "passive"))
      (node (ref "C17") (pin "1") (pinfunction "1_1") (pintype "passive"))
      (node (ref "C18") (pin "2") (pinfunction "2_2") (pintype "passive"))
      (node (ref "C2") (pin "2") (pinfunction "2_2") (pintype "passive"))
      (node (ref "C20") (pin "1") (pinfunction "1_1") (pintype "passive"))
      (node (ref "C21") (pin "1") (pinfunction "1_1") (pintype "passive"))
      (node (ref "C22") (pin "1") (pinfunction "1_1") (pintype "passive"))
      (node (ref "C23") (pin "1") (pinfunction "1_1") (pintype "passive"))
      (node (ref "C24") (pin "1") (pinfunction "1_1") (pintype "passive"))
      (node (ref "C26") (pin "2") (pinfunction "2_2") (pintype "passive"))
      (node (ref "C27") (pin "2") (pinfunction "2_2") (pintype "passive"))
      (node (ref "C28") (pin "2") (pinfunction "2_2") (pintype "passive"))
      (node (ref "C29") (pin "2") (pinfunction "2_2") (pintype "passive"))
      (node (ref "C3") (pin "2") (pinfunction "2_2") (pintype "passive"))
      (node (ref "C30") (pin "2") (pinfunction "2_2") (pintype "passive"))
      (node (ref "C31") (pin "2") (pinfunction "2_2") (pintype "passive"))
      (node (ref "C32") (pin "2") (pinfunction "2_2") (pintype "passive"))
      (node (ref "C33") (pin "2") (pinfunction "2_2") (pintype "passive"))
      (node (ref "C34") (pin "2") (pinfunction "2_2") (pintype "passive"))
      (node (ref "C35") (pin "1") (pinfunction "1_1") (pintype "passive"))
      (node (ref "C36") (pin "1") (pinfunction "1_1") (pintype "passive"))
      (node (ref "C37") (pin "1") (pinfunction "1_1") (pintype "passive"))
      (node (ref "C38") (pin "1") (pinfunction "1_1") (pintype "passive"))
      (node (ref "C39") (pin "1") (pinfunction "1_1") (pintype "passive"))
      (node (ref "C4") (pin "2") (pinfunction "2_2") (pintype "passive"))
      (node (ref "C40") (pin "1") (pinfunction "1_1") (pintype "passive"))
      (node (ref "C41") (pin "1") (pinfunction "1_1") (pintype "passive"))
      (node (ref "C42") (pin "1") (pinfunction "1_1") (pintype "passive"))
      (node (ref "C43") (pin "1") (pinfunction "1_1") (pintype "passive"))
      (node (ref "C44") (pin "1") (pinfunction "1_1") (pintype "passive"))
      (node (ref "C45") (pin "1") (pinfunction "1_1") (pintype "passive"))
      (node (ref "C46") (pin "1") (pinfunction "1_1") (pintype "passive"))
      (node (ref "C47") (pin "1") (pinfunction "1_1") (pintype "passive"))
      (node (ref "C48") (pin "1") (pinfunction "1_1") (pintype "passive"))
      (node (ref "C49") (pin "1") (pinfunction "1_1") (pintype "passive"))
      (node (ref "C5") (pin "1") (pinfunction "1_1") (pintype "passive"))
      (node (ref "C6") (pin "1") (pinfunction "1_1") (pintype "passive"))
      (node (ref "C7") (pin "2") (pinfunction "2_2") (pintype "passive"))
      (node (ref "C8") (pin "2") (pinfunction "2_2") (pintype "passive"))
      (node (ref "C9") (pin "2") (pinfunction "2_2") (pintype "passive"))
      (node (ref "J2") (pin "4") (pinfunction "4_4") (pintype "passive"))
      (node (ref "J3") (pin "4") (pinfunction "4_4") (pintype "passive"))
      (node (ref "R1") (pin "2") (pinfunction "2_2") (pintype "passive"))
      (node (ref "R11") (pin "1") (pinfunction "1_1") (pintype "passive"))
      (node (ref "R14") (pin "1") (pinfunction "1_1") (pintype "passive"))
      (node (ref "R20") (pin "1") (pinfunction "1_1") (pintype "passive"))
      (node (ref "R3") (pin "1") (pinfunction "1_1") (pintype "passive"))
      (node (ref "R4") (pin "1") (pinfunction "1_1") (pintype "passive"))
      (node (ref "R8") (pin "1") (pinfunction "1_1") (pintype "passive"))
      (node (ref "U1") (pin "116") (pinfunction "AGND_116") (pintype "passive"))
      (node (ref "U1") (pin "129") (pinfunction "EGND_129") (pintype "passive"))
      (node (ref "U2") (pin "2") (pinfunction "GND_2") (pintype "passive"))
      (node (ref "U4") (pin "2") (pinfunction "GND_2") (pintype "passive"))
      (node (ref "U5") (pin "2") (pinfunction "GND_2") (pintype "passive"))
      (node (ref "U7") (pin "1") (pinfunction "VSS_1") (pintype "passive"))
      (node (ref "Y2") (pin "2") (pinfunction "GND_2") (pintype "passive"))
      (node (ref "Y2") (pin "4") (pinfunction "GND_4") (pintype "passive"))
    )
    (net (code "53") (name "Net-(U1-EPHY-RTX)") (class "Default")
      (node (ref "R3") (pin "2") (pinfunction "2_2") (pintype "passive"))
      (node (ref "U1") (pin "94") (pinfunction "EPHY-RTX_94") (pintype "passive"))
    )
    (net (code "54") (name "Net-(U1-HBIAS)") (class "Default")
      (node (ref "C7") (pin "1") (pinfunction "1_1") (pintype "passive"))
      (node (ref "U1") (pin "119") (pinfunction "HBIAS_119") (pintype "passive"))
    )
    (net (code "55") (name "Net-(U1-HPVCCBP)") (class "Default")
      (node (ref "C5") (pin "2") (pinfunction "2_2") (pintype "passive"))
      (node (ref "C6") (pin "2") (pinfunction "2_2") (pintype "passive"))
      (node (ref "U1") (pin "123") (pinfunction "HPVCCBP_123") (pintype "passive"))
    )
    (net (code "56") (name "Net-(U1-MICIN1P)") (class "Default")
      (node (ref "C1") (pin "1") (pinfunction "1_1") (pintype "passive"))
      (node (ref "U1") (pin "113") (pinfunction "MICIN1P_113") (pintype "passive"))
    )
    (net (code "57") (name "Net-(U1-PF6)") (class "Default")
      (node (ref "R2") (pin "1") (pinfunction "1_1") (pintype "passive"))
      (node (ref "U1") (pin "100") (pinfunction "PF6_100") (pintype "passive"))
    )
    (net (code "58") (name "Net-(U1-RTC-VIO)") (class "Default")
      (node (ref "C8") (pin "1") (pinfunction "1_1") (pintype "passive"))
      (node (ref "U1") (pin "97") (pinfunction "RTC-VIO_97") (pintype "passive"))
    )
    (net (code "59") (name "Net-(U1-SZQ)") (class "Default")
      (node (ref "R4") (pin "2") (pinfunction "2_2") (pintype "passive"))
      (node (ref "U1") (pin "73") (pinfunction "SZQ_73") (pintype "passive"))
    )
    (net (code "60") (name "Net-(U1-VRA1)") (class "Default")
      (node (ref "C4") (pin "1") (pinfunction "1_1") (pintype "passive"))
      (node (ref "U1") (pin "117") (pinfunction "VRA1_117") (pintype "passive"))
    )
    (net (code "61") (name "Net-(U1-VRA2)") (class "Default")
      (node (ref "C3") (pin "1") (pinfunction "1_1") (pintype "passive"))
      (node (ref "R1") (pin "1") (pinfunction "1_1") (pintype "passive"))
      (node (ref "U1") (pin "118") (pinfunction "VRA2_118") (pintype "passive"))
    )
    (net (code "62") (name "Net-(U1-X24MIN)") (class "Default")
      (node (ref "C11") (pin "2") (pinfunction "2_2") (pintype "passive"))
      (node (ref "U1") (pin "75") (pinfunction "X24MIN_75") (pintype "passive"))
      (node (ref "Y2") (pin "3") (pinfunction "OSC2_3") (pintype "passive"))
    )
    (net (code "63") (name "Net-(U1-X24MOUT)") (class "Default")
      (node (ref "C12") (pin "1") (pinfunction "1_1") (pintype "passive"))
      (node (ref "U1") (pin "74") (pinfunction "X24MOUT_74") (pintype "passive"))
      (node (ref "Y2") (pin "1") (pinfunction "OSC1_1") (pintype "passive"))
    )
    (net (code "64") (name "Net-(U1-X32KIN)") (class "Default")
      (node (ref "C9") (pin "1") (pinfunction "1_1") (pintype "passive"))
      (node (ref "U1") (pin "96") (pinfunction "X32KIN_96") (pintype "passive"))
      (node (ref "Y1") (pin "2") (pinfunction "OSC2_2") (pintype "passive"))
    )
    (net (code "65") (name "Net-(U1-X32KOUT)") (class "Default")
      (node (ref "C10") (pin "1") (pinfunction "1_1") (pintype "passive"))
      (node (ref "U1") (pin "95") (pinfunction "X32KOUT_95") (pintype "passive"))
      (node (ref "Y1") (pin "1") (pinfunction "OSC1_1") (pintype "passive"))
    )
    (net (code "66") (name "Net-(U2-FB)") (class "Default")
      (node (ref "R10") (pin "1") (pinfunction "1_1") (pintype "passive"))
      (node (ref "R8") (pin "2") (pinfunction "2_2") (pintype "passive"))
      (node (ref "U2") (pin "5") (pinfunction "FB_5") (pintype "passive"))
    )
    (net (code "67") (name "Net-(U2-LX)") (class "Default")
      (node (ref "L1") (pin "1") (pinfunction "1_1") (pintype "passive"))
      (node (ref "U2") (pin "3") (pinfunction "LX_3") (pintype "passive"))
    )
    (net (code "68") (name "Net-(U4-FB)") (class "Default")
      (node (ref "R11") (pin "2") (pinfunction "2_2") (pintype "passive"))
      (node (ref "R12") (pin "1") (pinfunction "1_1") (pintype "passive"))
      (node (ref "U4") (pin "5") (pinfunction "FB_5") (pintype "passive"))
    )
    (net (code "69") (name "Net-(U4-LX)") (class "Default")
      (node (ref "L2") (pin "1") (pinfunction "1_1") (pintype "passive"))
      (node (ref "U4") (pin "3") (pinfunction "LX_3") (pintype "passive"))
    )
    (net (code "70") (name "Net-(U5-FB)") (class "Default")
      (node (ref "R14") (pin "2") (pinfunction "2_2") (pintype "passive"))
      (node (ref "R16") (pin "1") (pinfunction "1_1") (pintype "passive"))
      (node (ref "U5") (pin "5") (pinfunction "FB_5") (pintype "passive"))
    )
    (net (code "71") (name "Net-(U5-LX)") (class "Default")
      (node (ref "L3") (pin "1") (pinfunction "1_1") (pintype "passive"))
      (node (ref "U5") (pin "3") (pinfunction "LX_3") (pintype "passive"))
    )
    (net (code "72") (name "unconnected-(U1-EPHY-LINK-LED-Pad77)") (class "Default")
      (node (ref "U1") (pin "77") (pinfunction "EPHY-LINK-LED_77") (pintype "passive+no_connect"))
    )
    (net (code "73") (name "unconnected-(U1-EPHY-SPD-LED-Pad78)") (class "Default")
      (node (ref "U1") (pin "78") (pinfunction "EPHY-SPD-LED_78") (pintype "passive+no_connect"))
    )
    (net (code "74") (name "unconnected-(U1-LRADC0-Pad112)") (class "Default")
      (node (ref "U1") (pin "112") (pinfunction "LRADC0_112") (pintype "passive+no_connect"))
    )
    (net (code "75") (name "unconnected-(U1-PB2{slash}UART2_RTS{slash}PB_EINT2-Pad41)") (class "Default")
      (node (ref "U1") (pin "41") (pinfunction "PB2/UART2_RTS/PB_EINT2_41") (pintype "passive+no_connect"))
    )
    (net (code "76") (name "unconnected-(U1-PB3{slash}UART2_CTS{slash}PB_EINT3-Pad42)") (class "Default")
      (node (ref "U1") (pin "42") (pinfunction "PB3/UART2_CTS/PB_EINT3_42") (pintype "passive+no_connect"))
    )
    (net (code "77") (name "unconnected-(U1-PB6{slash}TWI0_SCK{slash}PB_EINT6-Pad45)") (class "Default")
      (node (ref "U1") (pin "45") (pinfunction "PB6/TWI0_SCK/PB_EINT6_45") (pintype "passive+no_connect"))
    )
    (net (code "78") (name "unconnected-(U1-PB7{slash}TWI0_SDA{slash}PB_EINT7-Pad46)") (class "Default")
      (node (ref "U1") (pin "46") (pinfunction "PB7/TWI0_SDA/PB_EINT7_46") (pintype "passive+no_connect"))
    )
    (net (code "79") (name "unconnected-(U1-PC0{slash}SDC2_CLK{slash}SPI_MISO-Pad52)") (class "Default")
      (node (ref "U1") (pin "52") (pinfunction "PC0/SDC2_CLK/SPI_MISO_52") (pintype "passive+no_connect"))
    )
    (net (code "80") (name "unconnected-(U1-PE0{slash}CSI_PCLK{slash}LCD_CLK-Pad37)") (class "Default")
      (node (ref "U1") (pin "37") (pinfunction "PE0/CSI_PCLK/LCD_CLK_37") (pintype "passive+no_connect"))
    )
    (net (code "81") (name "unconnected-(U1-PE1{slash}CSI_MCLK{slash}LCD_DE-Pad36)") (class "Default")
      (node (ref "U1") (pin "36") (pinfunction "PE1/CSI_MCLK/LCD_DE_36") (pintype "passive+no_connect"))
    )
    (net (code "82") (name "unconnected-(U1-PE2{slash}CSI_HSYNC{slash}LCD_HSYNC-Pad35)") (class "Default")
      (node (ref "U1") (pin "35") (pinfunction "PE2/CSI_HSYNC/LCD_HSYNC_35") (pintype "passive+no_connect"))
    )
    (net (code "83") (name "unconnected-(U1-PE3{slash}CSI_VSYNC{slash}LCD_VSYNC-Pad34)") (class "Default")
      (node (ref "U1") (pin "34") (pinfunction "PE3/CSI_VSYNC/LCD_VSYNC_34") (pintype "passive+no_connect"))
    )
    (net (code "84") (name "unconnected-(U1-PE4{slash}CSI_D0{slash}LCD_D2-Pad33)") (class "Default")
      (node (ref "U1") (pin "33") (pinfunction "PE4/CSI_D0/LCD_D2_33") (pintype "passive+no_connect"))
    )
    (net (code "85") (name "unconnected-(U1-PE5{slash}CSI_D1{slash}LCD_D3-Pad32)") (class "Default")
      (node (ref "U1") (pin "32") (pinfunction "PE5/CSI_D1/LCD_D3_32") (pintype "passive+no_connect"))
    )
    (net (code "86") (name "unconnected-(U1-PE6{slash}CSI_D2{slash}LCD_D4-Pad31)") (class "Default")
      (node (ref "U1") (pin "31") (pinfunction "PE6/CSI_D2/LCD_D4_31") (pintype "passive+no_connect"))
    )
    (net (code "87") (name "unconnected-(U1-PE7{slash}CSI_D3{slash}LCD_D5-Pad30)") (class "Default")
      (node (ref "U1") (pin "30") (pinfunction "PE7/CSI_D3/LCD_D5_30") (pintype "passive+no_connect"))
    )
    (net (code "88") (name "unconnected-(U1-PE8{slash}CSI_D4{slash}LCD_D6-Pad28)") (class "Default")
      (node (ref "U1") (pin "28") (pinfunction "PE8/CSI_D4/LCD_D6_28") (pintype "passive+no_connect"))
    )
    (net (code "89") (name "unconnected-(U1-PE9{slash}CSI_D5{slash}LCD_D7-Pad27)") (class "Default")
      (node (ref "U1") (pin "27") (pinfunction "PE9/CSI_D5/LCD_D7_27") (pintype "passive+no_connect"))
    )
    (net (code "90") (name "unconnected-(U1-PE10{slash}CSI_D6{slash}LCD_D10-Pad24)") (class "Default")
      (node (ref "U1") (pin "24") (pinfunction "PE10/CSI_D6/LCD_D10_24") (pintype "passive+no_connect"))
    )
    (net (code "91") (name "unconnected-(U1-PE11{slash}CSI_D7{slash}LCD_D11-Pad23)") (class "Default")
      (node (ref "U1") (pin "23") (pinfunction "PE11/CSI_D7/LCD_D11_23") (pintype "passive+no_connect"))
    )
    (net (code "92") (name "unconnected-(U1-PE12{slash}CSI_D8{slash}LCD_D12-Pad22)") (class "Default")
      (node (ref "U1") (pin "22") (pinfunction "PE12/CSI_D8/LCD_D12_22") (pintype "passive+no_connect"))
    )
    (net (code "93") (name "unconnected-(U1-PE13{slash}CSI_D9{slash}LCD_D13-Pad18)") (class "Default")
      (node (ref "U1") (pin "18") (pinfunction "PE13/CSI_D9/LCD_D13_18") (pintype "passive+no_connect"))
    )
    (net (code "94") (name "unconnected-(U1-PE19{slash}CSI_D15{slash}LCD_D21-Pad11)") (class "Default")
      (node (ref "U1") (pin "11") (pinfunction "PE19/CSI_D15/LCD_D21_11") (pintype "passive+no_connect"))
    )
    (net (code "95") (name "unconnected-(U1-PE20{slash}CSI_FIELD{slash}CSI_MIPI_MCLK-Pad10)") (class "Default")
      (node (ref "U1") (pin "10") (pinfunction "PE20/CSI_FIELD/CSI_MIPI_MCLK_10") (pintype "passive+no_connect"))
    )
    (net (code "96") (name "unconnected-(U1-PE23{slash}LCD_D22-Pad7)") (class "Default")
      (node (ref "U1") (pin "7") (pinfunction "PE23/LCD_D22_7") (pintype "passive+no_connect"))
    )
    (net (code "97") (name "unconnected-(U1-PE24{slash}LCD_D23-Pad6)") (class "Default")
      (node (ref "U1") (pin "6") (pinfunction "PE24/LCD_D23_6") (pintype "passive+no_connect"))
    )
  )
)
